# 5_Balancing.net
KiCad netlist of a schematic drawn in Altium Designer
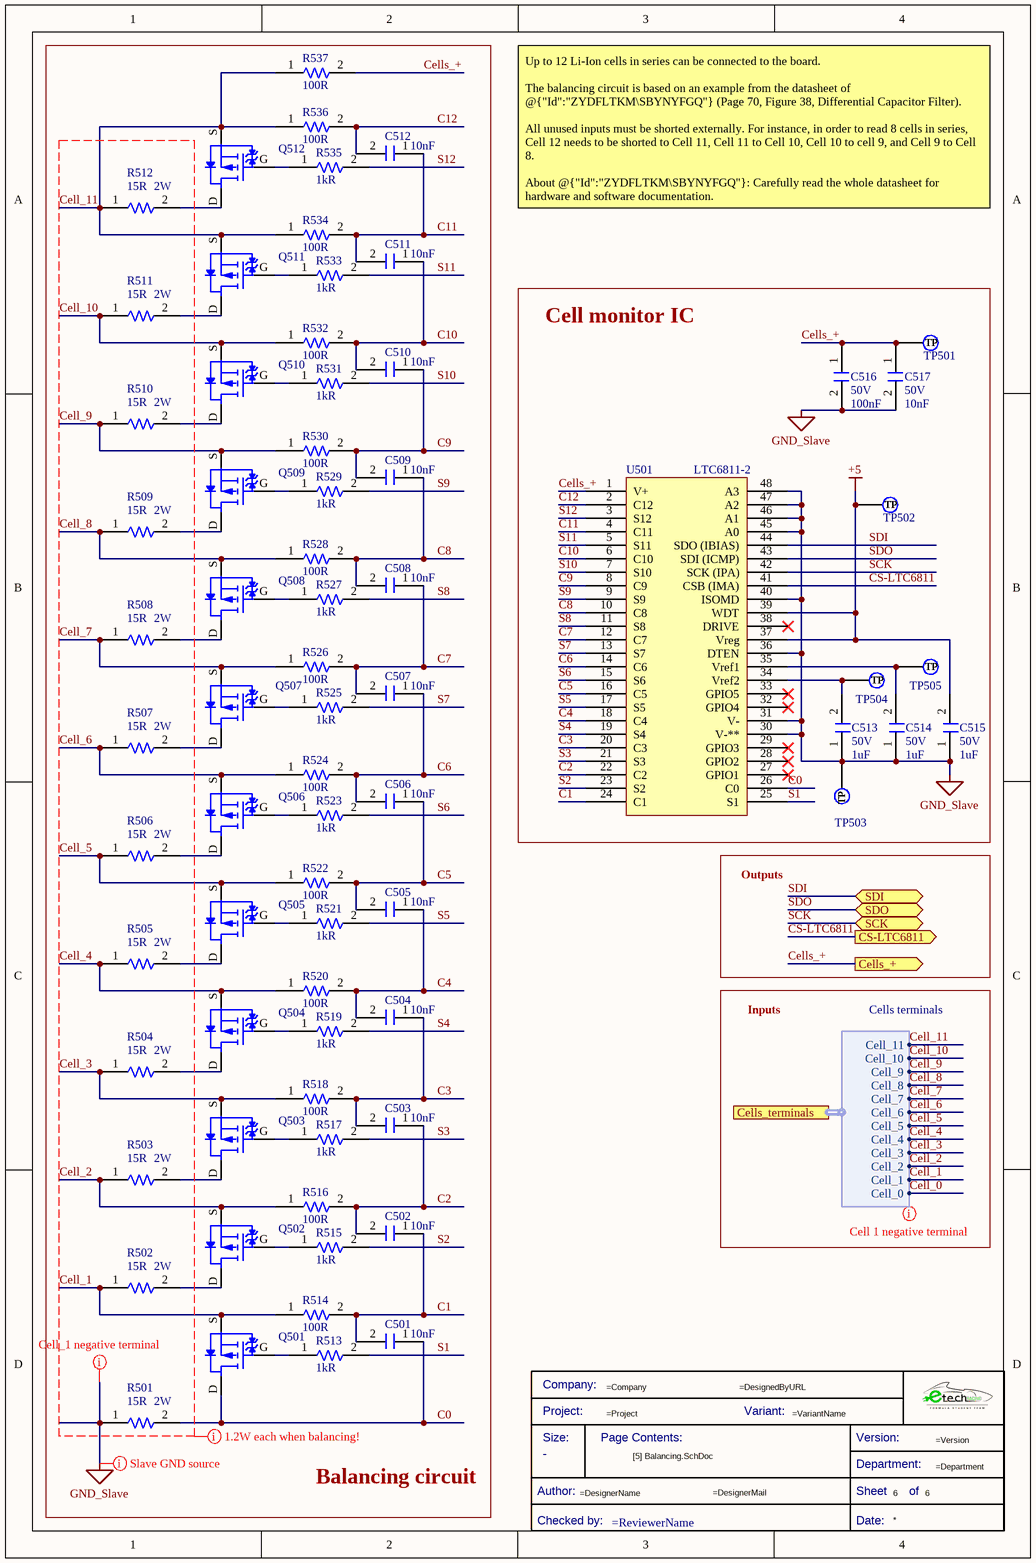
[diagram p0: [5] Balancing.SchDoc]

(export (version "E")
  (design (tool "Eeschema 10.0.6"))
  (components
    (comp (ref "*")
      (value "Title Block_template")
      (description "Standard Title Block")
      (fields (field (name "SIZE") "-"))
      (libsource (lib "e-Tech_Racing") (part "Title Block_template"))
    )
    (comp (ref "C501")
      (value "885012207092")
      (footprint "C0805FNPC-R")
      (description "Cap, 0.01ΜF, 50V, 10%, X7R, 0805")
      (fields
        (field (name "TOLERANCE") "10%")
        (field (name "CAPACITANCE") "10nF")
        (field (name ".CREATOR") "DR")
      )
      (libsource (lib "Passives") (part "C10n-50V-0805FNPC-X7R"))
    )
    (comp (ref "C502")
      (value "885012207092")
      (footprint "C0805FNPC-R")
      (description "Cap, 0.01ΜF, 50V, 10%, X7R, 0805")
      (fields
        (field (name "TOLERANCE") "10%")
        (field (name "CAPACITANCE") "10nF")
        (field (name ".CREATOR") "DR")
      )
      (libsource (lib "Passives") (part "C10n-50V-0805FNPC-X7R"))
    )
    (comp (ref "C503")
      (value "885012207092")
      (footprint "C0805FNPC-R")
      (description "Cap, 0.01ΜF, 50V, 10%, X7R, 0805")
      (fields
        (field (name "TOLERANCE") "10%")
        (field (name "CAPACITANCE") "10nF")
        (field (name ".CREATOR") "DR")
      )
      (libsource (lib "Passives") (part "C10n-50V-0805FNPC-X7R"))
    )
    (comp (ref "C504")
      (value "885012207092")
      (footprint "C0805FNPC-R")
      (description "Cap, 0.01ΜF, 50V, 10%, X7R, 0805")
      (fields
        (field (name "TOLERANCE") "10%")
        (field (name "CAPACITANCE") "10nF")
        (field (name ".CREATOR") "DR")
      )
      (libsource (lib "Passives") (part "C10n-50V-0805FNPC-X7R"))
    )
    (comp (ref "C505")
      (value "885012207092")
      (footprint "C0805FNPC-R")
      (description "Cap, 0.01ΜF, 50V, 10%, X7R, 0805")
      (fields
        (field (name "TOLERANCE") "10%")
        (field (name "CAPACITANCE") "10nF")
        (field (name ".CREATOR") "DR")
      )
      (libsource (lib "Passives") (part "C10n-50V-0805FNPC-X7R"))
    )
    (comp (ref "C506")
      (value "885012207092")
      (footprint "C0805FNPC-R")
      (description "Cap, 0.01ΜF, 50V, 10%, X7R, 0805")
      (fields
        (field (name "TOLERANCE") "10%")
        (field (name "CAPACITANCE") "10nF")
        (field (name ".CREATOR") "DR")
      )
      (libsource (lib "Passives") (part "C10n-50V-0805FNPC-X7R"))
    )
    (comp (ref "C507")
      (value "885012207092")
      (footprint "C0805FNPC-R")
      (description "Cap, 0.01ΜF, 50V, 10%, X7R, 0805")
      (fields
        (field (name "TOLERANCE") "10%")
        (field (name "CAPACITANCE") "10nF")
        (field (name ".CREATOR") "DR")
      )
      (libsource (lib "Passives") (part "C10n-50V-0805FNPC-X7R"))
    )
    (comp (ref "C508")
      (value "885012207092")
      (footprint "C0805FNPC-R")
      (description "Cap, 0.01ΜF, 50V, 10%, X7R, 0805")
      (fields
        (field (name "TOLERANCE") "10%")
        (field (name "CAPACITANCE") "10nF")
        (field (name ".CREATOR") "DR")
      )
      (libsource (lib "Passives") (part "C10n-50V-0805FNPC-X7R"))
    )
    (comp (ref "C509")
      (value "885012207092")
      (footprint "C0805FNPC-R")
      (description "Cap, 0.01ΜF, 50V, 10%, X7R, 0805")
      (fields
        (field (name "TOLERANCE") "10%")
        (field (name "CAPACITANCE") "10nF")
        (field (name ".CREATOR") "DR")
      )
      (libsource (lib "Passives") (part "C10n-50V-0805FNPC-X7R"))
    )
    (comp (ref "C510")
      (value "885012207092")
      (footprint "C0805FNPC-R")
      (description "Cap, 0.01ΜF, 50V, 10%, X7R, 0805")
      (fields
        (field (name "TOLERANCE") "10%")
        (field (name "CAPACITANCE") "10nF")
        (field (name ".CREATOR") "DR")
      )
      (libsource (lib "Passives") (part "C10n-50V-0805FNPC-X7R"))
    )
    (comp (ref "C511")
      (value "885012207092")
      (footprint "C0805FNPC-R")
      (description "Cap, 0.01ΜF, 50V, 10%, X7R, 0805")
      (fields
        (field (name "TOLERANCE") "10%")
        (field (name "CAPACITANCE") "10nF")
        (field (name ".CREATOR") "DR")
      )
      (libsource (lib "Passives") (part "C10n-50V-0805FNPC-X7R"))
    )
    (comp (ref "C512")
      (value "885012207092")
      (footprint "C0805FNPC-R")
      (description "Cap, 0.01ΜF, 50V, 10%, X7R, 0805")
      (fields
        (field (name "TOLERANCE") "10%")
        (field (name "CAPACITANCE") "10nF")
        (field (name ".CREATOR") "DR")
      )
      (libsource (lib "Passives") (part "C10n-50V-0805FNPC-X7R"))
    )
    (comp (ref "C513")
      (value "885012207103")
      (footprint "C0805FNPC-R")
      (fields
        (field (name "VOLTAGE RATING") "50V")
        (field (name "TOLERANCE") "10%")
        (field (name "CAPACITANCE") "1uF")
        (field (name ".CREATOR") "GP")
      )
      (libsource (lib "Passives") (part "C1u-50V-0805FNPC-X7R"))
    )
    (comp (ref "C514")
      (value "885012207103")
      (footprint "C0805FNPC-R")
      (fields
        (field (name "VOLTAGE RATING") "50V")
        (field (name "TOLERANCE") "10%")
        (field (name "CAPACITANCE") "1uF")
        (field (name ".CREATOR") "GP")
      )
      (libsource (lib "Passives") (part "C1u-50V-0805FNPC-X7R"))
    )
    (comp (ref "C515")
      (value "885012207103")
      (footprint "C0805FNPC-R")
      (fields
        (field (name "VOLTAGE RATING") "50V")
        (field (name "TOLERANCE") "10%")
        (field (name "CAPACITANCE") "1uF")
        (field (name ".CREATOR") "GP")
      )
      (libsource (lib "Passives") (part "C1u-50V-0805FNPC-X7R"))
    )
    (comp (ref "C516")
      (value "885012207098")
      (footprint "C0805FNPC-R")
      (description "Cap, 0.1ΜF, 50V, 10%, X7R, 0805")
      (fields
        (field (name "VOLTAGE RATING") "50V")
        (field (name "TOLERANCE") "10%")
        (field (name "CAPACITANCE") "100nF")
        (field (name ".CREATOR") "DR")
      )
      (libsource (lib "Passives") (part "C100n-50V-0805FNPC-X7R"))
    )
    (comp (ref "C517")
      (value "885012207092")
      (footprint "C0805FNPC-R")
      (description "Cap, 0.01ΜF, 50V, 10%, X7R, 0805")
      (fields
        (field (name "VOLTAGE RATING") "50V")
        (field (name "TOLERANCE") "10%")
        (field (name "CAPACITANCE") "10nF")
        (field (name ".CREATOR") "DR")
      )
      (libsource (lib "Passives") (part "C10n-50V-0805FNPC-X7R"))
    )
    (comp (ref "Q501")
      (value "BSS308PE")
      (footprint "TRT-PCH-2/30-BSS")
      (description "Infineon’s highly innovative OptiMOS™ families include p-channel power MOSFETs, SOT-23-3, RoHS")
      (fields
        (field (name "MANUFACTURER") "Infineon")
        (field (name "MANUFACTURER PART NUMBER") "BSS308PEH6327")
        (field (name ".CREATOR") "DO")
      )
      (libsource (lib "Semiconductor") (part "TRT-PCH-2/30-BSS"))
    )
    (comp (ref "Q502")
      (value "BSS308PE")
      (footprint "TRT-PCH-2/30-BSS")
      (description "Infineon’s highly innovative OptiMOS™ families include p-channel power MOSFETs, SOT-23-3, RoHS")
      (fields
        (field (name "MANUFACTURER") "Infineon")
        (field (name "MANUFACTURER PART NUMBER") "BSS308PEH6327")
        (field (name ".CREATOR") "DO")
      )
      (libsource (lib "Semiconductor") (part "TRT-PCH-2/30-BSS"))
    )
    (comp (ref "Q503")
      (value "BSS308PE")
      (footprint "TRT-PCH-2/30-BSS")
      (description "Infineon’s highly innovative OptiMOS™ families include p-channel power MOSFETs, SOT-23-3, RoHS")
      (fields
        (field (name "MANUFACTURER") "Infineon")
        (field (name "MANUFACTURER PART NUMBER") "BSS308PEH6327")
        (field (name ".CREATOR") "DO")
      )
      (libsource (lib "Semiconductor") (part "TRT-PCH-2/30-BSS"))
    )
    (comp (ref "Q504")
      (value "BSS308PE")
      (footprint "TRT-PCH-2/30-BSS")
      (description "Infineon’s highly innovative OptiMOS™ families include p-channel power MOSFETs, SOT-23-3, RoHS")
      (fields
        (field (name "MANUFACTURER") "Infineon")
        (field (name "MANUFACTURER PART NUMBER") "BSS308PEH6327")
        (field (name ".CREATOR") "DO")
      )
      (libsource (lib "Semiconductor") (part "TRT-PCH-2/30-BSS"))
    )
    (comp (ref "Q505")
      (value "BSS308PE")
      (footprint "TRT-PCH-2/30-BSS")
      (description "Infineon’s highly innovative OptiMOS™ families include p-channel power MOSFETs, SOT-23-3, RoHS")
      (fields
        (field (name "MANUFACTURER") "Infineon")
        (field (name "MANUFACTURER PART NUMBER") "BSS308PEH6327")
        (field (name ".CREATOR") "DO")
      )
      (libsource (lib "Semiconductor") (part "TRT-PCH-2/30-BSS"))
    )
    (comp (ref "Q506")
      (value "BSS308PE")
      (footprint "TRT-PCH-2/30-BSS")
      (description "Infineon’s highly innovative OptiMOS™ families include p-channel power MOSFETs, SOT-23-3, RoHS")
      (fields
        (field (name "MANUFACTURER") "Infineon")
        (field (name "MANUFACTURER PART NUMBER") "BSS308PEH6327")
        (field (name ".CREATOR") "DO")
      )
      (libsource (lib "Semiconductor") (part "TRT-PCH-2/30-BSS"))
    )
    (comp (ref "Q507")
      (value "BSS308PE")
      (footprint "TRT-PCH-2/30-BSS")
      (description "Infineon’s highly innovative OptiMOS™ families include p-channel power MOSFETs, SOT-23-3, RoHS")
      (fields
        (field (name "MANUFACTURER") "Infineon")
        (field (name "MANUFACTURER PART NUMBER") "BSS308PEH6327")
        (field (name ".CREATOR") "DO")
      )
      (libsource (lib "Semiconductor") (part "TRT-PCH-2/30-BSS"))
    )
    (comp (ref "Q508")
      (value "BSS308PE")
      (footprint "TRT-PCH-2/30-BSS")
      (description "Infineon’s highly innovative OptiMOS™ families include p-channel power MOSFETs, SOT-23-3, RoHS")
      (fields
        (field (name "MANUFACTURER") "Infineon")
        (field (name "MANUFACTURER PART NUMBER") "BSS308PEH6327")
        (field (name ".CREATOR") "DO")
      )
      (libsource (lib "Semiconductor") (part "TRT-PCH-2/30-BSS"))
    )
    (comp (ref "Q509")
      (value "BSS308PE")
      (footprint "TRT-PCH-2/30-BSS")
      (description "Infineon’s highly innovative OptiMOS™ families include p-channel power MOSFETs, SOT-23-3, RoHS")
      (fields
        (field (name "MANUFACTURER") "Infineon")
        (field (name "MANUFACTURER PART NUMBER") "BSS308PEH6327")
        (field (name ".CREATOR") "DO")
      )
      (libsource (lib "Semiconductor") (part "TRT-PCH-2/30-BSS"))
    )
    (comp (ref "Q510")
      (value "BSS308PE")
      (footprint "TRT-PCH-2/30-BSS")
      (description "Infineon’s highly innovative OptiMOS™ families include p-channel power MOSFETs, SOT-23-3, RoHS")
      (fields
        (field (name "MANUFACTURER") "Infineon")
        (field (name "MANUFACTURER PART NUMBER") "BSS308PEH6327")
        (field (name ".CREATOR") "DO")
      )
      (libsource (lib "Semiconductor") (part "TRT-PCH-2/30-BSS"))
    )
    (comp (ref "Q511")
      (value "BSS308PE")
      (footprint "TRT-PCH-2/30-BSS")
      (description "Infineon’s highly innovative OptiMOS™ families include p-channel power MOSFETs, SOT-23-3, RoHS")
      (fields
        (field (name "MANUFACTURER") "Infineon")
        (field (name "MANUFACTURER PART NUMBER") "BSS308PEH6327")
        (field (name ".CREATOR") "DO")
      )
      (libsource (lib "Semiconductor") (part "TRT-PCH-2/30-BSS"))
    )
    (comp (ref "Q512")
      (value "BSS308PE")
      (footprint "TRT-PCH-2/30-BSS")
      (description "Infineon’s highly innovative OptiMOS™ families include p-channel power MOSFETs, SOT-23-3, RoHS")
      (fields
        (field (name "MANUFACTURER") "Infineon")
        (field (name "MANUFACTURER PART NUMBER") "BSS308PEH6327")
        (field (name ".CREATOR") "DO")
      )
      (libsource (lib "Semiconductor") (part "TRT-PCH-2/30-BSS"))
    )
    (comp (ref "R501")
      (value "15R")
      (footprint "R2512FTK")
      (description "Res Thick Film 2512 15 Ohm 1% 2W ±100ppm/C Pad SMD T/R")
      (fields
        (field (name "TOLERANCE") "1%")
        (field (name "MAX POWER DISSIPATION") "2W")
        (field (name "Comment") "352115RFT")
        (field (name ".CREATOR") "DR")
      )
      (libsource (lib "Passives") (part "R15-2512FTK"))
    )
    (comp (ref "R502")
      (value "15R")
      (footprint "R2512FTK")
      (description "Res Thick Film 2512 15 Ohm 1% 2W ±100ppm/C Pad SMD T/R")
      (fields
        (field (name "TOLERANCE") "1%")
        (field (name "MAX POWER DISSIPATION") "2W")
        (field (name "Comment") "352115RFT")
        (field (name ".CREATOR") "DR")
      )
      (libsource (lib "Passives") (part "R15-2512FTK"))
    )
    (comp (ref "R503")
      (value "15R")
      (footprint "R2512FTK")
      (description "Res Thick Film 2512 15 Ohm 1% 2W ±100ppm/C Pad SMD T/R")
      (fields
        (field (name "TOLERANCE") "1%")
        (field (name "MAX POWER DISSIPATION") "2W")
        (field (name "Comment") "352115RFT")
        (field (name ".CREATOR") "DR")
      )
      (libsource (lib "Passives") (part "R15-2512FTK"))
    )
    (comp (ref "R504")
      (value "15R")
      (footprint "R2512FTK")
      (description "Res Thick Film 2512 15 Ohm 1% 2W ±100ppm/C Pad SMD T/R")
      (fields
        (field (name "TOLERANCE") "1%")
        (field (name "MAX POWER DISSIPATION") "2W")
        (field (name "Comment") "352115RFT")
        (field (name ".CREATOR") "DR")
      )
      (libsource (lib "Passives") (part "R15-2512FTK"))
    )
    (comp (ref "R505")
      (value "15R")
      (footprint "R2512FTK")
      (description "Res Thick Film 2512 15 Ohm 1% 2W ±100ppm/C Pad SMD T/R")
      (fields
        (field (name "TOLERANCE") "1%")
        (field (name "MAX POWER DISSIPATION") "2W")
        (field (name "Comment") "352115RFT")
        (field (name ".CREATOR") "DR")
      )
      (libsource (lib "Passives") (part "R15-2512FTK"))
    )
    (comp (ref "R506")
      (value "15R")
      (footprint "R2512FTK")
      (description "Res Thick Film 2512 15 Ohm 1% 2W ±100ppm/C Pad SMD T/R")
      (fields
        (field (name "TOLERANCE") "1%")
        (field (name "MAX POWER DISSIPATION") "2W")
        (field (name "Comment") "352115RFT")
        (field (name ".CREATOR") "DR")
      )
      (libsource (lib "Passives") (part "R15-2512FTK"))
    )
    (comp (ref "R507")
      (value "15R")
      (footprint "R2512FTK")
      (description "Res Thick Film 2512 15 Ohm 1% 2W ±100ppm/C Pad SMD T/R")
      (fields
        (field (name "TOLERANCE") "1%")
        (field (name "MAX POWER DISSIPATION") "2W")
        (field (name "Comment") "352115RFT")
        (field (name ".CREATOR") "DR")
      )
      (libsource (lib "Passives") (part "R15-2512FTK"))
    )
    (comp (ref "R508")
      (value "15R")
      (footprint "R2512FTK")
      (description "Res Thick Film 2512 15 Ohm 1% 2W ±100ppm/C Pad SMD T/R")
      (fields
        (field (name "TOLERANCE") "1%")
        (field (name "MAX POWER DISSIPATION") "2W")
        (field (name "Comment") "352115RFT")
        (field (name ".CREATOR") "DR")
      )
      (libsource (lib "Passives") (part "R15-2512FTK"))
    )
    (comp (ref "R509")
      (value "15R")
      (footprint "R2512FTK")
      (description "Res Thick Film 2512 15 Ohm 1% 2W ±100ppm/C Pad SMD T/R")
      (fields
        (field (name "TOLERANCE") "1%")
        (field (name "MAX POWER DISSIPATION") "2W")
        (field (name "Comment") "352115RFT")
        (field (name ".CREATOR") "DR")
      )
      (libsource (lib "Passives") (part "R15-2512FTK"))
    )
    (comp (ref "R510")
      (value "15R")
      (footprint "R2512FTK")
      (description "Res Thick Film 2512 15 Ohm 1% 2W ±100ppm/C Pad SMD T/R")
      (fields
        (field (name "TOLERANCE") "1%")
        (field (name "MAX POWER DISSIPATION") "2W")
        (field (name "Comment") "352115RFT")
        (field (name ".CREATOR") "DR")
      )
      (libsource (lib "Passives") (part "R15-2512FTK"))
    )
    (comp (ref "R511")
      (value "15R")
      (footprint "R2512FTK")
      (description "Res Thick Film 2512 15 Ohm 1% 2W ±100ppm/C Pad SMD T/R")
      (fields
        (field (name "TOLERANCE") "1%")
        (field (name "MAX POWER DISSIPATION") "2W")
        (field (name "Comment") "352115RFT")
        (field (name ".CREATOR") "DR")
      )
      (libsource (lib "Passives") (part "R15-2512FTK"))
    )
    (comp (ref "R512")
      (value "15R")
      (footprint "R2512FTK")
      (description "Res Thick Film 2512 15 Ohm 1% 2W ±100ppm/C Pad SMD T/R")
      (fields
        (field (name "TOLERANCE") "1%")
        (field (name "MAX POWER DISSIPATION") "2W")
        (field (name "Comment") "352115RFT")
        (field (name ".CREATOR") "DR")
      )
      (libsource (lib "Passives") (part "R15-2512FTK"))
    )
    (comp (ref "R513")
      (value "CR0805-JW-102ELF")
      (footprint "R0805FTK")
      (description "Res Thick Film 0805 1K Ohm 5% 1/8W ±200ppm/°C Molded SMD SMD Paper Tape on Plastic Reel")
      (fields
        (field (name "TOLERANCE") "5%")
        (field (name "RESISTANCE") "1kR")
        (field (name ".CREATOR") "GP")
      )
      (libsource (lib "Passives") (part "R1k-0805FTK"))
    )
    (comp (ref "R514")
      (value "CR0805-FX-1000ELF")
      (footprint "R0805FTK")
      (description "Res Thick Film 0805 100 Ohm 1% 1/8W ±100ppm/°C Molded SMD SMD Paper Tape on Plastic Reel")
      (fields
        (field (name "TOLERANCE") "1%")
        (field (name "RESISTANCE") "100R")
        (field (name ".CREATOR") "DR")
      )
      (libsource (lib "Passives") (part "R100-0805FTK"))
    )
    (comp (ref "R515")
      (value "CR0805-JW-102ELF")
      (footprint "R0805FTK")
      (description "Res Thick Film 0805 1K Ohm 5% 1/8W ±200ppm/°C Molded SMD SMD Paper Tape on Plastic Reel")
      (fields
        (field (name "TOLERANCE") "5%")
        (field (name "RESISTANCE") "1kR")
        (field (name ".CREATOR") "GP")
      )
      (libsource (lib "Passives") (part "R1k-0805FTK"))
    )
    (comp (ref "R516")
      (value "CR0805-FX-1000ELF")
      (footprint "R0805FTK")
      (description "Res Thick Film 0805 100 Ohm 1% 1/8W ±100ppm/°C Molded SMD SMD Paper Tape on Plastic Reel")
      (fields
        (field (name "TOLERANCE") "1%")
        (field (name "RESISTANCE") "100R")
        (field (name ".CREATOR") "DR")
      )
      (libsource (lib "Passives") (part "R100-0805FTK"))
    )
    (comp (ref "R517")
      (value "CR0805-JW-102ELF")
      (footprint "R0805FTK")
      (description "Res Thick Film 0805 1K Ohm 5% 1/8W ±200ppm/°C Molded SMD SMD Paper Tape on Plastic Reel")
      (fields
        (field (name "TOLERANCE") "5%")
        (field (name "RESISTANCE") "1kR")
        (field (name ".CREATOR") "GP")
      )
      (libsource (lib "Passives") (part "R1k-0805FTK"))
    )
    (comp (ref "R518")
      (value "CR0805-FX-1000ELF")
      (footprint "R0805FTK")
      (description "Res Thick Film 0805 100 Ohm 1% 1/8W ±100ppm/°C Molded SMD SMD Paper Tape on Plastic Reel")
      (fields
        (field (name "TOLERANCE") "1%")
        (field (name "RESISTANCE") "100R")
        (field (name ".CREATOR") "DR")
      )
      (libsource (lib "Passives") (part "R100-0805FTK"))
    )
    (comp (ref "R519")
      (value "CR0805-JW-102ELF")
      (footprint "R0805FTK")
      (description "Res Thick Film 0805 1K Ohm 5% 1/8W ±200ppm/°C Molded SMD SMD Paper Tape on Plastic Reel")
      (fields
        (field (name "TOLERANCE") "5%")
        (field (name "RESISTANCE") "1kR")
        (field (name ".CREATOR") "GP")
      )
      (libsource (lib "Passives") (part "R1k-0805FTK"))
    )
    (comp (ref "R520")
      (value "CR0805-FX-1000ELF")
      (footprint "R0805FTK")
      (description "Res Thick Film 0805 100 Ohm 1% 1/8W ±100ppm/°C Molded SMD SMD Paper Tape on Plastic Reel")
      (fields
        (field (name "TOLERANCE") "1%")
        (field (name "RESISTANCE") "100R")
        (field (name ".CREATOR") "DR")
      )
      (libsource (lib "Passives") (part "R100-0805FTK"))
    )
    (comp (ref "R521")
      (value "CR0805-JW-102ELF")
      (footprint "R0805FTK")
      (description "Res Thick Film 0805 1K Ohm 5% 1/8W ±200ppm/°C Molded SMD SMD Paper Tape on Plastic Reel")
      (fields
        (field (name "TOLERANCE") "5%")
        (field (name "RESISTANCE") "1kR")
        (field (name ".CREATOR") "GP")
      )
      (libsource (lib "Passives") (part "R1k-0805FTK"))
    )
    (comp (ref "R522")
      (value "CR0805-FX-1000ELF")
      (footprint "R0805FTK")
      (description "Res Thick Film 0805 100 Ohm 1% 1/8W ±100ppm/°C Molded SMD SMD Paper Tape on Plastic Reel")
      (fields
        (field (name "TOLERANCE") "1%")
        (field (name "RESISTANCE") "100R")
        (field (name ".CREATOR") "DR")
      )
      (libsource (lib "Passives") (part "R100-0805FTK"))
    )
    (comp (ref "R523")
      (value "CR0805-JW-102ELF")
      (footprint "R0805FTK")
      (description "Res Thick Film 0805 1K Ohm 5% 1/8W ±200ppm/°C Molded SMD SMD Paper Tape on Plastic Reel")
      (fields
        (field (name "TOLERANCE") "5%")
        (field (name "RESISTANCE") "1kR")
        (field (name ".CREATOR") "GP")
      )
      (libsource (lib "Passives") (part "R1k-0805FTK"))
    )
    (comp (ref "R524")
      (value "CR0805-FX-1000ELF")
      (footprint "R0805FTK")
      (description "Res Thick Film 0805 100 Ohm 1% 1/8W ±100ppm/°C Molded SMD SMD Paper Tape on Plastic Reel")
      (fields
        (field (name "TOLERANCE") "1%")
        (field (name "RESISTANCE") "100R")
        (field (name ".CREATOR") "DR")
      )
      (libsource (lib "Passives") (part "R100-0805FTK"))
    )
    (comp (ref "R525")
      (value "CR0805-JW-102ELF")
      (footprint "R0805FTK")
      (description "Res Thick Film 0805 1K Ohm 5% 1/8W ±200ppm/°C Molded SMD SMD Paper Tape on Plastic Reel")
      (fields
        (field (name "TOLERANCE") "5%")
        (field (name "RESISTANCE") "1kR")
        (field (name ".CREATOR") "GP")
      )
      (libsource (lib "Passives") (part "R1k-0805FTK"))
    )
    (comp (ref "R526")
      (value "CR0805-FX-1000ELF")
      (footprint "R0805FTK")
      (description "Res Thick Film 0805 100 Ohm 1% 1/8W ±100ppm/°C Molded SMD SMD Paper Tape on Plastic Reel")
      (fields
        (field (name "TOLERANCE") "1%")
        (field (name "RESISTANCE") "100R")
        (field (name ".CREATOR") "DR")
      )
      (libsource (lib "Passives") (part "R100-0805FTK"))
    )
    (comp (ref "R527")
      (value "CR0805-JW-102ELF")
      (footprint "R0805FTK")
      (description "Res Thick Film 0805 1K Ohm 5% 1/8W ±200ppm/°C Molded SMD SMD Paper Tape on Plastic Reel")
      (fields
        (field (name "TOLERANCE") "5%")
        (field (name "RESISTANCE") "1kR")
        (field (name ".CREATOR") "GP")
      )
      (libsource (lib "Passives") (part "R1k-0805FTK"))
    )
    (comp (ref "R528")
      (value "CR0805-FX-1000ELF")
      (footprint "R0805FTK")
      (description "Res Thick Film 0805 100 Ohm 1% 1/8W ±100ppm/°C Molded SMD SMD Paper Tape on Plastic Reel")
      (fields
        (field (name "TOLERANCE") "1%")
        (field (name "RESISTANCE") "100R")
        (field (name ".CREATOR") "DR")
      )
      (libsource (lib "Passives") (part "R100-0805FTK"))
    )
    (comp (ref "R529")
      (value "CR0805-JW-102ELF")
      (footprint "R0805FTK")
      (description "Res Thick Film 0805 1K Ohm 5% 1/8W ±200ppm/°C Molded SMD SMD Paper Tape on Plastic Reel")
      (fields
        (field (name "TOLERANCE") "5%")
        (field (name "RESISTANCE") "1kR")
        (field (name ".CREATOR") "GP")
      )
      (libsource (lib "Passives") (part "R1k-0805FTK"))
    )
    (comp (ref "R530")
      (value "CR0805-FX-1000ELF")
      (footprint "R0805FTK")
      (description "Res Thick Film 0805 100 Ohm 1% 1/8W ±100ppm/°C Molded SMD SMD Paper Tape on Plastic Reel")
      (fields
        (field (name "TOLERANCE") "1%")
        (field (name "RESISTANCE") "100R")
        (field (name ".CREATOR") "DR")
      )
      (libsource (lib "Passives") (part "R100-0805FTK"))
    )
    (comp (ref "R531")
      (value "CR0805-JW-102ELF")
      (footprint "R0805FTK")
      (description "Res Thick Film 0805 1K Ohm 5% 1/8W ±200ppm/°C Molded SMD SMD Paper Tape on Plastic Reel")
      (fields
        (field (name "TOLERANCE") "5%")
        (field (name "RESISTANCE") "1kR")
        (field (name ".CREATOR") "GP")
      )
      (libsource (lib "Passives") (part "R1k-0805FTK"))
    )
    (comp (ref "R532")
      (value "CR0805-FX-1000ELF")
      (footprint "R0805FTK")
      (description "Res Thick Film 0805 100 Ohm 1% 1/8W ±100ppm/°C Molded SMD SMD Paper Tape on Plastic Reel")
      (fields
        (field (name "TOLERANCE") "1%")
        (field (name "RESISTANCE") "100R")
        (field (name ".CREATOR") "DR")
      )
      (libsource (lib "Passives") (part "R100-0805FTK"))
    )
    (comp (ref "R533")
      (value "CR0805-JW-102ELF")
      (footprint "R0805FTK")
      (description "Res Thick Film 0805 1K Ohm 5% 1/8W ±200ppm/°C Molded SMD SMD Paper Tape on Plastic Reel")
      (fields
        (field (name "TOLERANCE") "5%")
        (field (name "RESISTANCE") "1kR")
        (field (name ".CREATOR") "GP")
      )
      (libsource (lib "Passives") (part "R1k-0805FTK"))
    )
    (comp (ref "R534")
      (value "CR0805-FX-1000ELF")
      (footprint "R0805FTK")
      (description "Res Thick Film 0805 100 Ohm 1% 1/8W ±100ppm/°C Molded SMD SMD Paper Tape on Plastic Reel")
      (fields
        (field (name "TOLERANCE") "1%")
        (field (name "RESISTANCE") "100R")
        (field (name ".CREATOR") "DR")
      )
      (libsource (lib "Passives") (part "R100-0805FTK"))
    )
    (comp (ref "R535")
      (value "CR0805-JW-102ELF")
      (footprint "R0805FTK")
      (description "Res Thick Film 0805 1K Ohm 5% 1/8W ±200ppm/°C Molded SMD SMD Paper Tape on Plastic Reel")
      (fields
        (field (name "TOLERANCE") "5%")
        (field (name "RESISTANCE") "1kR")
        (field (name ".CREATOR") "GP")
      )
      (libsource (lib "Passives") (part "R1k-0805FTK"))
    )
    (comp (ref "R536")
      (value "CR0805-FX-1000ELF")
      (footprint "R0805FTK")
      (description "Res Thick Film 0805 100 Ohm 1% 1/8W ±100ppm/°C Molded SMD SMD Paper Tape on Plastic Reel")
      (fields
        (field (name "TOLERANCE") "1%")
        (field (name "RESISTANCE") "100R")
        (field (name ".CREATOR") "DR")
      )
      (libsource (lib "Passives") (part "R100-0805FTK"))
    )
    (comp (ref "R537")
      (value "CR0805-FX-1000ELF")
      (footprint "R0805FTK")
      (description "Res Thick Film 0805 100 Ohm 1% 1/8W ±100ppm/°C Molded SMD SMD Paper Tape on Plastic Reel")
      (fields
        (field (name "TOLERANCE") "1%")
        (field (name "RESISTANCE") "100R")
        (field (name ".CREATOR") "DR")
      )
      (libsource (lib "Passives") (part "R100-0805FTK"))
    )
    (comp (ref "TP501")
      (value "TestPoint")
      (footprint "TestPoint")
      (description "Test Point 1x1 mm")
      (fields (field (name ".CREATOR") "GP") (field (name ".PCBCHECK") "GP") (field (name ".SCHCHECK") "GP"))
      (libsource (lib "e-Tech_Racing") (part "TestPoint"))
    )
    (comp (ref "TP502")
      (value "TestPoint")
      (footprint "TestPoint")
      (description "Test Point 1x1 mm")
      (fields (field (name ".CREATOR") "GP") (field (name ".PCBCHECK") "GP") (field (name ".SCHCHECK") "GP"))
      (libsource (lib "e-Tech_Racing") (part "TestPoint"))
    )
    (comp (ref "TP503")
      (value "TestPoint")
      (footprint "TestPoint")
      (description "Test Point 1x1 mm")
      (fields (field (name ".CREATOR") "GP") (field (name ".PCBCHECK") "GP") (field (name ".SCHCHECK") "GP"))
      (libsource (lib "e-Tech_Racing") (part "TestPoint"))
    )
    (comp (ref "TP504")
      (value "TestPoint")
      (footprint "TestPoint")
      (description "Test Point 1x1 mm")
      (fields (field (name ".CREATOR") "GP") (field (name ".PCBCHECK") "GP") (field (name ".SCHCHECK") "GP"))
      (libsource (lib "e-Tech_Racing") (part "TestPoint"))
    )
    (comp (ref "TP505")
      (value "TestPoint")
      (footprint "TestPoint")
      (description "Test Point 1x1 mm")
      (fields (field (name ".CREATOR") "GP") (field (name ".PCBCHECK") "GP") (field (name ".SCHCHECK") "GP"))
      (libsource (lib "e-Tech_Racing") (part "TestPoint"))
    )
    (comp (ref "U501")
      (value "LTC6811-2")
      (footprint "U_LTC6811G-2")
      (description "Sc-Automotive Multicell Battery Stack Monitor With Addressable Isospi Interface")
      (fields (field (name "MANUFACTURER PART NUMBER 1") "LTC6811-2") (field (name ".CREATOR") "GP"))
      (libsource (lib "Integrated circuits") (part "U_LTC6811-2"))
    )
  )
  (nets
    (net (code "3") (name "+5") (class "Default")
      (node (ref "C515") (pin "2") (pinfunction "2_2") (pintype "passive"))
      (node (ref "TP502") (pin "1") (pinfunction "TP_1") (pintype "passive"))
      (node (ref "U501") (pin "37") (pinfunction "Vreg_37") (pintype "passive"))
      (node (ref "U501") (pin "39") (pinfunction "WDT_39") (pintype "passive"))
    )
    (net (code "4") (name "/C0") (class "Default")
      (node (ref "C501") (pin "1") (pinfunction "1_1") (pintype "passive"))
      (node (ref "Q501") (pin "D") (pinfunction "D_D") (pintype "passive"))
      (node (ref "R501") (pin "2") (pinfunction "2_2") (pintype "passive"))
      (node (ref "U501") (pin "26") (pinfunction "C0_26") (pintype "passive"))
    )
    (net (code "5") (name "/C1") (class "Default")
      (node (ref "C501") (pin "2") (pinfunction "2_2") (pintype "passive"))
      (node (ref "C502") (pin "1") (pinfunction "1_1") (pintype "passive"))
      (node (ref "R514") (pin "2") (pinfunction "2_2") (pintype "passive"))
      (node (ref "U501") (pin "24") (pinfunction "C1_24") (pintype "passive"))
    )
    (net (code "6") (name "/C2") (class "Default")
      (node (ref "C502") (pin "2") (pinfunction "2_2") (pintype "passive"))
      (node (ref "C503") (pin "1") (pinfunction "1_1") (pintype "passive"))
      (node (ref "R516") (pin "2") (pinfunction "2_2") (pintype "passive"))
      (node (ref "U501") (pin "22") (pinfunction "C2_22") (pintype "passive"))
    )
    (net (code "7") (name "/C3") (class "Default")
      (node (ref "C503") (pin "2") (pinfunction "2_2") (pintype "passive"))
      (node (ref "C504") (pin "1") (pinfunction "1_1") (pintype "passive"))
      (node (ref "R518") (pin "2") (pinfunction "2_2") (pintype "passive"))
      (node (ref "U501") (pin "20") (pinfunction "C3_20") (pintype "passive"))
    )
    (net (code "8") (name "/C4") (class "Default")
      (node (ref "C504") (pin "2") (pinfunction "2_2") (pintype "passive"))
      (node (ref "C505") (pin "1") (pinfunction "1_1") (pintype "passive"))
      (node (ref "R520") (pin "2") (pinfunction "2_2") (pintype "passive"))
      (node (ref "U501") (pin "18") (pinfunction "C4_18") (pintype "passive"))
    )
    (net (code "9") (name "/C5") (class "Default")
      (node (ref "C505") (pin "2") (pinfunction "2_2") (pintype "passive"))
      (node (ref "C506") (pin "1") (pinfunction "1_1") (pintype "passive"))
      (node (ref "R522") (pin "2") (pinfunction "2_2") (pintype "passive"))
      (node (ref "U501") (pin "16") (pinfunction "C5_16") (pintype "passive"))
    )
    (net (code "10") (name "/C6") (class "Default")
      (node (ref "C506") (pin "2") (pinfunction "2_2") (pintype "passive"))
      (node (ref "C507") (pin "1") (pinfunction "1_1") (pintype "passive"))
      (node (ref "R524") (pin "2") (pinfunction "2_2") (pintype "passive"))
      (node (ref "U501") (pin "14") (pinfunction "C6_14") (pintype "passive"))
    )
    (net (code "11") (name "/C7") (class "Default")
      (node (ref "C507") (pin "2") (pinfunction "2_2") (pintype "passive"))
      (node (ref "C508") (pin "1") (pinfunction "1_1") (pintype "passive"))
      (node (ref "R526") (pin "2") (pinfunction "2_2") (pintype "passive"))
      (node (ref "U501") (pin "12") (pinfunction "C7_12") (pintype "passive"))
    )
    (net (code "12") (name "/C8") (class "Default")
      (node (ref "C508") (pin "2") (pinfunction "2_2") (pintype "passive"))
      (node (ref "C509") (pin "1") (pinfunction "1_1") (pintype "passive"))
      (node (ref "R528") (pin "2") (pinfunction "2_2") (pintype "passive"))
      (node (ref "U501") (pin "10") (pinfunction "C8_10") (pintype "passive"))
    )
    (net (code "13") (name "/C9") (class "Default")
      (node (ref "C509") (pin "2") (pinfunction "2_2") (pintype "passive"))
      (node (ref "C510") (pin "1") (pinfunction "1_1") (pintype "passive"))
      (node (ref "R530") (pin "2") (pinfunction "2_2") (pintype "passive"))
      (node (ref "U501") (pin "8") (pinfunction "C9_8") (pintype "passive"))
    )
    (net (code "14") (name "/C10") (class "Default")
      (node (ref "C510") (pin "2") (pinfunction "2_2") (pintype "passive"))
      (node (ref "C511") (pin "1") (pinfunction "1_1") (pintype "passive"))
      (node (ref "R532") (pin "2") (pinfunction "2_2") (pintype "passive"))
      (node (ref "U501") (pin "6") (pinfunction "C10_6") (pintype "passive"))
    )
    (net (code "15") (name "/C11") (class "Default")
      (node (ref "C511") (pin "2") (pinfunction "2_2") (pintype "passive"))
      (node (ref "C512") (pin "1") (pinfunction "1_1") (pintype "passive"))
      (node (ref "R534") (pin "2") (pinfunction "2_2") (pintype "passive"))
      (node (ref "U501") (pin "4") (pinfunction "C11_4") (pintype "passive"))
    )
    (net (code "16") (name "/C12") (class "Default")
      (node (ref "C512") (pin "2") (pinfunction "2_2") (pintype "passive"))
      (node (ref "R536") (pin "2") (pinfunction "2_2") (pintype "passive"))
      (node (ref "U501") (pin "2") (pinfunction "C12_2") (pintype "passive"))
    )
    (net (code "17") (name "/CS-LTC6811") (class "Default")
      (node (ref "U501") (pin "41") (pinfunction "CSB_(IMA)_41") (pintype "passive"))
    )
    (net (code "19") (name "/Cell_1") (class "Default")
      (node (ref "Q501") (pin "S") (pinfunction "S_S") (pintype "passive"))
      (node (ref "R502") (pin "1") (pinfunction "1_1") (pintype "passive"))
      (node (ref "R514") (pin "1") (pinfunction "1_1") (pintype "passive"))
    )
    (net (code "20") (name "/Cell_2") (class "Default")
      (node (ref "Q502") (pin "S") (pinfunction "S_S") (pintype "passive"))
      (node (ref "R503") (pin "1") (pinfunction "1_1") (pintype "passive"))
      (node (ref "R516") (pin "1") (pinfunction "1_1") (pintype "passive"))
    )
    (net (code "21") (name "/Cell_3") (class "Default")
      (node (ref "Q503") (pin "S") (pinfunction "S_S") (pintype "passive"))
      (node (ref "R504") (pin "1") (pinfunction "1_1") (pintype "passive"))
      (node (ref "R518") (pin "1") (pinfunction "1_1") (pintype "passive"))
    )
    (net (code "22") (name "/Cell_4") (class "Default")
      (node (ref "Q504") (pin "S") (pinfunction "S_S") (pintype "passive"))
      (node (ref "R505") (pin "1") (pinfunction "1_1") (pintype "passive"))
      (node (ref "R520") (pin "1") (pinfunction "1_1") (pintype "passive"))
    )
    (net (code "23") (name "/Cell_5") (class "Default")
      (node (ref "Q505") (pin "S") (pinfunction "S_S") (pintype "passive"))
      (node (ref "R506") (pin "1") (pinfunction "1_1") (pintype "passive"))
      (node (ref "R522") (pin "1") (pinfunction "1_1") (pintype "passive"))
    )
    (net (code "24") (name "/Cell_6") (class "Default")
      (node (ref "Q506") (pin "S") (pinfunction "S_S") (pintype "passive"))
      (node (ref "R507") (pin "1") (pinfunction "1_1") (pintype "passive"))
      (node (ref "R524") (pin "1") (pinfunction "1_1") (pintype "passive"))
    )
    (net (code "25") (name "/Cell_7") (class "Default")
      (node (ref "Q507") (pin "S") (pinfunction "S_S") (pintype "passive"))
      (node (ref "R508") (pin "1") (pinfunction "1_1") (pintype "passive"))
      (node (ref "R526") (pin "1") (pinfunction "1_1") (pintype "passive"))
    )
    (net (code "26") (name "/Cell_8") (class "Default")
      (node (ref "Q508") (pin "S") (pinfunction "S_S") (pintype "passive"))
      (node (ref "R509") (pin "1") (pinfunction "1_1") (pintype "passive"))
      (node (ref "R528") (pin "1") (pinfunction "1_1") (pintype "passive"))
    )
    (net (code "27") (name "/Cell_9") (class "Default")
      (node (ref "Q509") (pin "S") (pinfunction "S_S") (pintype "passive"))
      (node (ref "R510") (pin "1") (pinfunction "1_1") (pintype "passive"))
      (node (ref "R530") (pin "1") (pinfunction "1_1") (pintype "passive"))
    )
    (net (code "28") (name "/Cell_10") (class "Default")
      (node (ref "Q510") (pin "S") (pinfunction "S_S") (pintype "passive"))
      (node (ref "R511") (pin "1") (pinfunction "1_1") (pintype "passive"))
      (node (ref "R532") (pin "1") (pinfunction "1_1") (pintype "passive"))
    )
    (net (code "29") (name "/Cell_11") (class "Default")
      (node (ref "Q511") (pin "S") (pinfunction "S_S") (pintype "passive"))
      (node (ref "Q512") (pin "S") (pinfunction "S_S") (pintype "passive"))
      (node (ref "R512") (pin "1") (pinfunction "1_1") (pintype "passive"))
      (node (ref "R534") (pin "1") (pinfunction "1_1") (pintype "passive"))
      (node (ref "R536") (pin "1") (pinfunction "1_1") (pintype "passive"))
      (node (ref "R537") (pin "1") (pinfunction "1_1") (pintype "passive"))
    )
    (net (code "30") (name "/Cells_+") (class "Default")
      (node (ref "C516") (pin "1") (pinfunction "1_1") (pintype "passive"))
      (node (ref "C517") (pin "1") (pinfunction "1_1") (pintype "passive"))
      (node (ref "R537") (pin "2") (pinfunction "2_2") (pintype "passive"))
      (node (ref "TP501") (pin "1") (pinfunction "TP_1") (pintype "passive"))
      (node (ref "U501") (pin "1") (pinfunction "V+_1") (pintype "passive"))
    )
    (net (code "31") (name "/S1") (class "Default")
      (node (ref "R513") (pin "2") (pinfunction "2_2") (pintype "passive"))
      (node (ref "U501") (pin "25") (pinfunction "S1_25") (pintype "passive"))
    )
    (net (code "32") (name "/S2") (class "Default")
      (node (ref "R515") (pin "2") (pinfunction "2_2") (pintype "passive"))
      (node (ref "U501") (pin "23") (pinfunction "S2_23") (pintype "passive"))
    )
    (net (code "33") (name "/S3") (class "Default")
      (node (ref "R517") (pin "2") (pinfunction "2_2") (pintype "passive"))
      (node (ref "U501") (pin "21") (pinfunction "S3_21") (pintype "passive"))
    )
    (net (code "34") (name "/S4") (class "Default")
      (node (ref "R519") (pin "2") (pinfunction "2_2") (pintype "passive"))
      (node (ref "U501") (pin "19") (pinfunction "S4_19") (pintype "passive"))
    )
    (net (code "35") (name "/S5") (class "Default")
      (node (ref "R521") (pin "2") (pinfunction "2_2") (pintype "passive"))
      (node (ref "U501") (pin "17") (pinfunction "S5_17") (pintype "passive"))
    )
    (net (code "36") (name "/S6") (class "Default")
      (node (ref "R523") (pin "2") (pinfunction "2_2") (pintype "passive"))
      (node (ref "U501") (pin "15") (pinfunction "S6_15") (pintype "passive"))
    )
    (net (code "37") (name "/S7") (class "Default")
      (node (ref "R525") (pin "2") (pinfunction "2_2") (pintype "passive"))
      (node (ref "U501") (pin "13") (pinfunction "S7_13") (pintype "passive"))
    )
    (net (code "38") (name "/S8") (class "Default")
      (node (ref "R527") (pin "2") (pinfunction "2_2") (pintype "passive"))
      (node (ref "U501") (pin "11") (pinfunction "S8_11") (pintype "passive"))
    )
    (net (code "39") (name "/S9") (class "Default")
      (node (ref "R529") (pin "2") (pinfunction "2_2") (pintype "passive"))
      (node (ref "U501") (pin "9") (pinfunction "S9_9") (pintype "passive"))
    )
    (net (code "40") (name "/S10") (class "Default")
      (node (ref "R531") (pin "2") (pinfunction "2_2") (pintype "passive"))
      (node (ref "U501") (pin "7") (pinfunction "S10_7") (pintype "passive"))
    )
    (net (code "41") (name "/S11") (class "Default")
      (node (ref "R533") (pin "2") (pinfunction "2_2") (pintype "passive"))
      (node (ref "U501") (pin "5") (pinfunction "S11_5") (pintype "passive"))
    )
    (net (code "42") (name "/S12") (class "Default")
      (node (ref "R535") (pin "2") (pinfunction "2_2") (pintype "passive"))
      (node (ref "U501") (pin "3") (pinfunction "S12_3") (pintype "passive"))
    )
    (net (code "43") (name "/SCK") (class "Default")
      (node (ref "U501") (pin "42") (pinfunction "SCK_(IPA)_42") (pintype "passive"))
    )
    (net (code "44") (name "/SDI") (class "Default")
      (node (ref "U501") (pin "44") (pinfunction "SDO_(IBIAS)_44") (pintype "passive"))
    )
    (net (code "45") (name "/SDO") (class "Default")
      (node (ref "U501") (pin "43") (pinfunction "SDI_(ICMP)_43") (pintype "passive"))
    )
    (net (code "47") (name "GND_Slave") (class "Default")
      (node (ref "C513") (pin "1") (pinfunction "1_1") (pintype "passive"))
      (node (ref "C514") (pin "1") (pinfunction "1_1") (pintype "passive"))
      (node (ref "C515") (pin "1") (pinfunction "1_1") (pintype "passive"))
      (node (ref "C516") (pin "2") (pinfunction "2_2") (pintype "passive"))
      (node (ref "C517") (pin "2") (pinfunction "2_2") (pintype "passive"))
      (node (ref "R501") (pin "1") (pinfunction "1_1") (pintype "passive"))
      (node (ref "TP503") (pin "1") (pinfunction "TP_1") (pintype "passive"))
      (node (ref "U501") (pin "30") (pinfunction "V-**_30") (pintype "passive"))
      (node (ref "U501") (pin "31") (pinfunction "V-_31") (pintype "passive"))
      (node (ref "U501") (pin "36") (pinfunction "DTEN_36") (pintype "passive"))
      (node (ref "U501") (pin "40") (pinfunction "ISOMD_40") (pintype "passive"))
      (node (ref "U501") (pin "45") (pinfunction "A0_45") (pintype "passive"))
      (node (ref "U501") (pin "46") (pinfunction "A1_46") (pintype "passive"))
      (node (ref "U501") (pin "47") (pinfunction "A2_47") (pintype "passive"))
      (node (ref "U501") (pin "48") (pinfunction "A3_48") (pintype "passive"))
    )
    (net (code "48") (name "Net-(Q501-PadG)") (class "Default")
      (node (ref "Q501") (pin "G") (pinfunction "G_G") (pintype "passive"))
      (node (ref "R513") (pin "1") (pinfunction "1_1") (pintype "passive"))
    )
    (net (code "49") (name "Net-(Q502-PadD)") (class "Default")
      (node (ref "Q502") (pin "D") (pinfunction "D_D") (pintype "passive"))
      (node (ref "R502") (pin "2") (pinfunction "2_2") (pintype "passive"))
    )
    (net (code "50") (name "Net-(Q502-PadG)") (class "Default")
      (node (ref "Q502") (pin "G") (pinfunction "G_G") (pintype "passive"))
      (node (ref "R515") (pin "1") (pinfunction "1_1") (pintype "passive"))
    )
    (net (code "51") (name "Net-(Q503-PadD)") (class "Default")
      (node (ref "Q503") (pin "D") (pinfunction "D_D") (pintype "passive"))
      (node (ref "R503") (pin "2") (pinfunction "2_2") (pintype "passive"))
    )
    (net (code "52") (name "Net-(Q503-PadG)") (class "Default")
      (node (ref "Q503") (pin "G") (pinfunction "G_G") (pintype "passive"))
      (node (ref "R517") (pin "1") (pinfunction "1_1") (pintype "passive"))
    )
    (net (code "53") (name "Net-(Q504-PadD)") (class "Default")
      (node (ref "Q504") (pin "D") (pinfunction "D_D") (pintype "passive"))
      (node (ref "R504") (pin "2") (pinfunction "2_2") (pintype "passive"))
    )
    (net (code "54") (name "Net-(Q504-PadG)") (class "Default")
      (node (ref "Q504") (pin "G") (pinfunction "G_G") (pintype "passive"))
      (node (ref "R519") (pin "1") (pinfunction "1_1") (pintype "passive"))
    )
    (net (code "55") (name "Net-(Q505-PadD)") (class "Default")
      (node (ref "Q505") (pin "D") (pinfunction "D_D") (pintype "passive"))
      (node (ref "R505") (pin "2") (pinfunction "2_2") (pintype "passive"))
    )
    (net (code "56") (name "Net-(Q505-PadG)") (class "Default")
      (node (ref "Q505") (pin "G") (pinfunction "G_G") (pintype "passive"))
      (node (ref "R521") (pin "1") (pinfunction "1_1") (pintype "passive"))
    )
    (net (code "57") (name "Net-(Q506-PadD)") (class "Default")
      (node (ref "Q506") (pin "D") (pinfunction "D_D") (pintype "passive"))
      (node (ref "R506") (pin "2") (pinfunction "2_2") (pintype "passive"))
    )
    (net (code "58") (name "Net-(Q506-PadG)") (class "Default")
      (node (ref "Q506") (pin "G") (pinfunction "G_G") (pintype "passive"))
      (node (ref "R523") (pin "1") (pinfunction "1_1") (pintype "passive"))
    )
    (net (code "59") (name "Net-(Q507-PadD)") (class "Default")
      (node (ref "Q507") (pin "D") (pinfunction "D_D") (pintype "passive"))
      (node (ref "R507") (pin "2") (pinfunction "2_2") (pintype "passive"))
    )
    (net (code "60") (name "Net-(Q507-PadG)") (class "Default")
      (node (ref "Q507") (pin "G") (pinfunction "G_G") (pintype "passive"))
      (node (ref "R525") (pin "1") (pinfunction "1_1") (pintype "passive"))
    )
    (net (code "61") (name "Net-(Q508-PadD)") (class "Default")
      (node (ref "Q508") (pin "D") (pinfunction "D_D") (pintype "passive"))
      (node (ref "R508") (pin "2") (pinfunction "2_2") (pintype "passive"))
    )
    (net (code "62") (name "Net-(Q508-PadG)") (class "Default")
      (node (ref "Q508") (pin "G") (pinfunction "G_G") (pintype "passive"))
      (node (ref "R527") (pin "1") (pinfunction "1_1") (pintype "passive"))
    )
    (net (code "63") (name "Net-(Q509-PadD)") (class "Default")
      (node (ref "Q509") (pin "D") (pinfunction "D_D") (pintype "passive"))
      (node (ref "R509") (pin "2") (pinfunction "2_2") (pintype "passive"))
    )
    (net (code "64") (name "Net-(Q509-PadG)") (class "Default")
      (node (ref "Q509") (pin "G") (pinfunction "G_G") (pintype "passive"))
      (node (ref "R529") (pin "1") (pinfunction "1_1") (pintype "passive"))
    )
    (net (code "65") (name "Net-(Q510-PadD)") (class "Default")
      (node (ref "Q510") (pin "D") (pinfunction "D_D") (pintype "passive"))
      (node (ref "R510") (pin "2") (pinfunction "2_2") (pintype "passive"))
    )
    (net (code "66") (name "Net-(Q510-PadG)") (class "Default")
      (node (ref "Q510") (pin "G") (pinfunction "G_G") (pintype "passive"))
      (node (ref "R531") (pin "1") (pinfunction "1_1") (pintype "passive"))
    )
    (net (code "67") (name "Net-(Q511-PadD)") (class "Default")
      (node (ref "Q511") (pin "D") (pinfunction "D_D") (pintype "passive"))
      (node (ref "R511") (pin "2") (pinfunction "2_2") (pintype "passive"))
    )
    (net (code "68") (name "Net-(Q511-PadG)") (class "Default")
      (node (ref "Q511") (pin "G") (pinfunction "G_G") (pintype "passive"))
      (node (ref "R533") (pin "1") (pinfunction "1_1") (pintype "passive"))
    )
    (net (code "69") (name "Net-(Q512-PadD)") (class "Default")
      (node (ref "Q512") (pin "D") (pinfunction "D_D") (pintype "passive"))
      (node (ref "R512") (pin "2") (pinfunction "2_2") (pintype "passive"))
    )
    (net (code "70") (name "Net-(Q512-PadG)") (class "Default")
      (node (ref "Q512") (pin "G") (pinfunction "G_G") (pintype "passive"))
      (node (ref "R535") (pin "1") (pinfunction "1_1") (pintype "passive"))
    )
    (net (code "71") (name "Net-(TP504-TP)") (class "Default")
      (node (ref "C513") (pin "2") (pinfunction "2_2") (pintype "passive"))
      (node (ref "TP504") (pin "1") (pinfunction "TP_1") (pintype "passive"))
      (node (ref "U501") (pin "34") (pinfunction "Vref2_34") (pintype "passive"))
    )
    (net (code "72") (name "Net-(TP505-TP)") (class "Default")
      (node (ref "C514") (pin "2") (pinfunction "2_2") (pintype "passive"))
      (node (ref "TP505") (pin "1") (pinfunction "TP_1") (pintype "passive"))
      (node (ref "U501") (pin "35") (pinfunction "Vref1_35") (pintype "passive"))
    )
    (net (code "73") (name "unconnected-(U501-DRIVE-Pad38)") (class "Default")
      (node (ref "U501") (pin "38") (pinfunction "DRIVE_38") (pintype "passive+no_connect"))
    )
    (net (code "74") (name "unconnected-(U501-GPIO1-Pad27)") (class "Default")
      (node (ref "U501") (pin "27") (pinfunction "GPIO1_27") (pintype "passive+no_connect"))
    )
    (net (code "75") (name "unconnected-(U501-GPIO2-Pad28)") (class "Default")
      (node (ref "U501") (pin "28") (pinfunction "GPIO2_28") (pintype "passive+no_connect"))
    )
    (net (code "76") (name "unconnected-(U501-GPIO3-Pad29)") (class "Default")
      (node (ref "U501") (pin "29") (pinfunction "GPIO3_29") (pintype "passive+no_connect"))
    )
    (net (code "77") (name "unconnected-(U501-GPIO4-Pad32)") (class "Default")
      (node (ref "U501") (pin "32") (pinfunction "GPIO4_32") (pintype "passive+no_connect"))
    )
    (net (code "78") (name "unconnected-(U501-GPIO5-Pad33)") (class "Default")
      (node (ref "U501") (pin "33") (pinfunction "GPIO5_33") (pintype "passive+no_connect"))
    )
  )
)
